# FPGA.net
KiCad netlist of a schematic drawn in Altium Designer
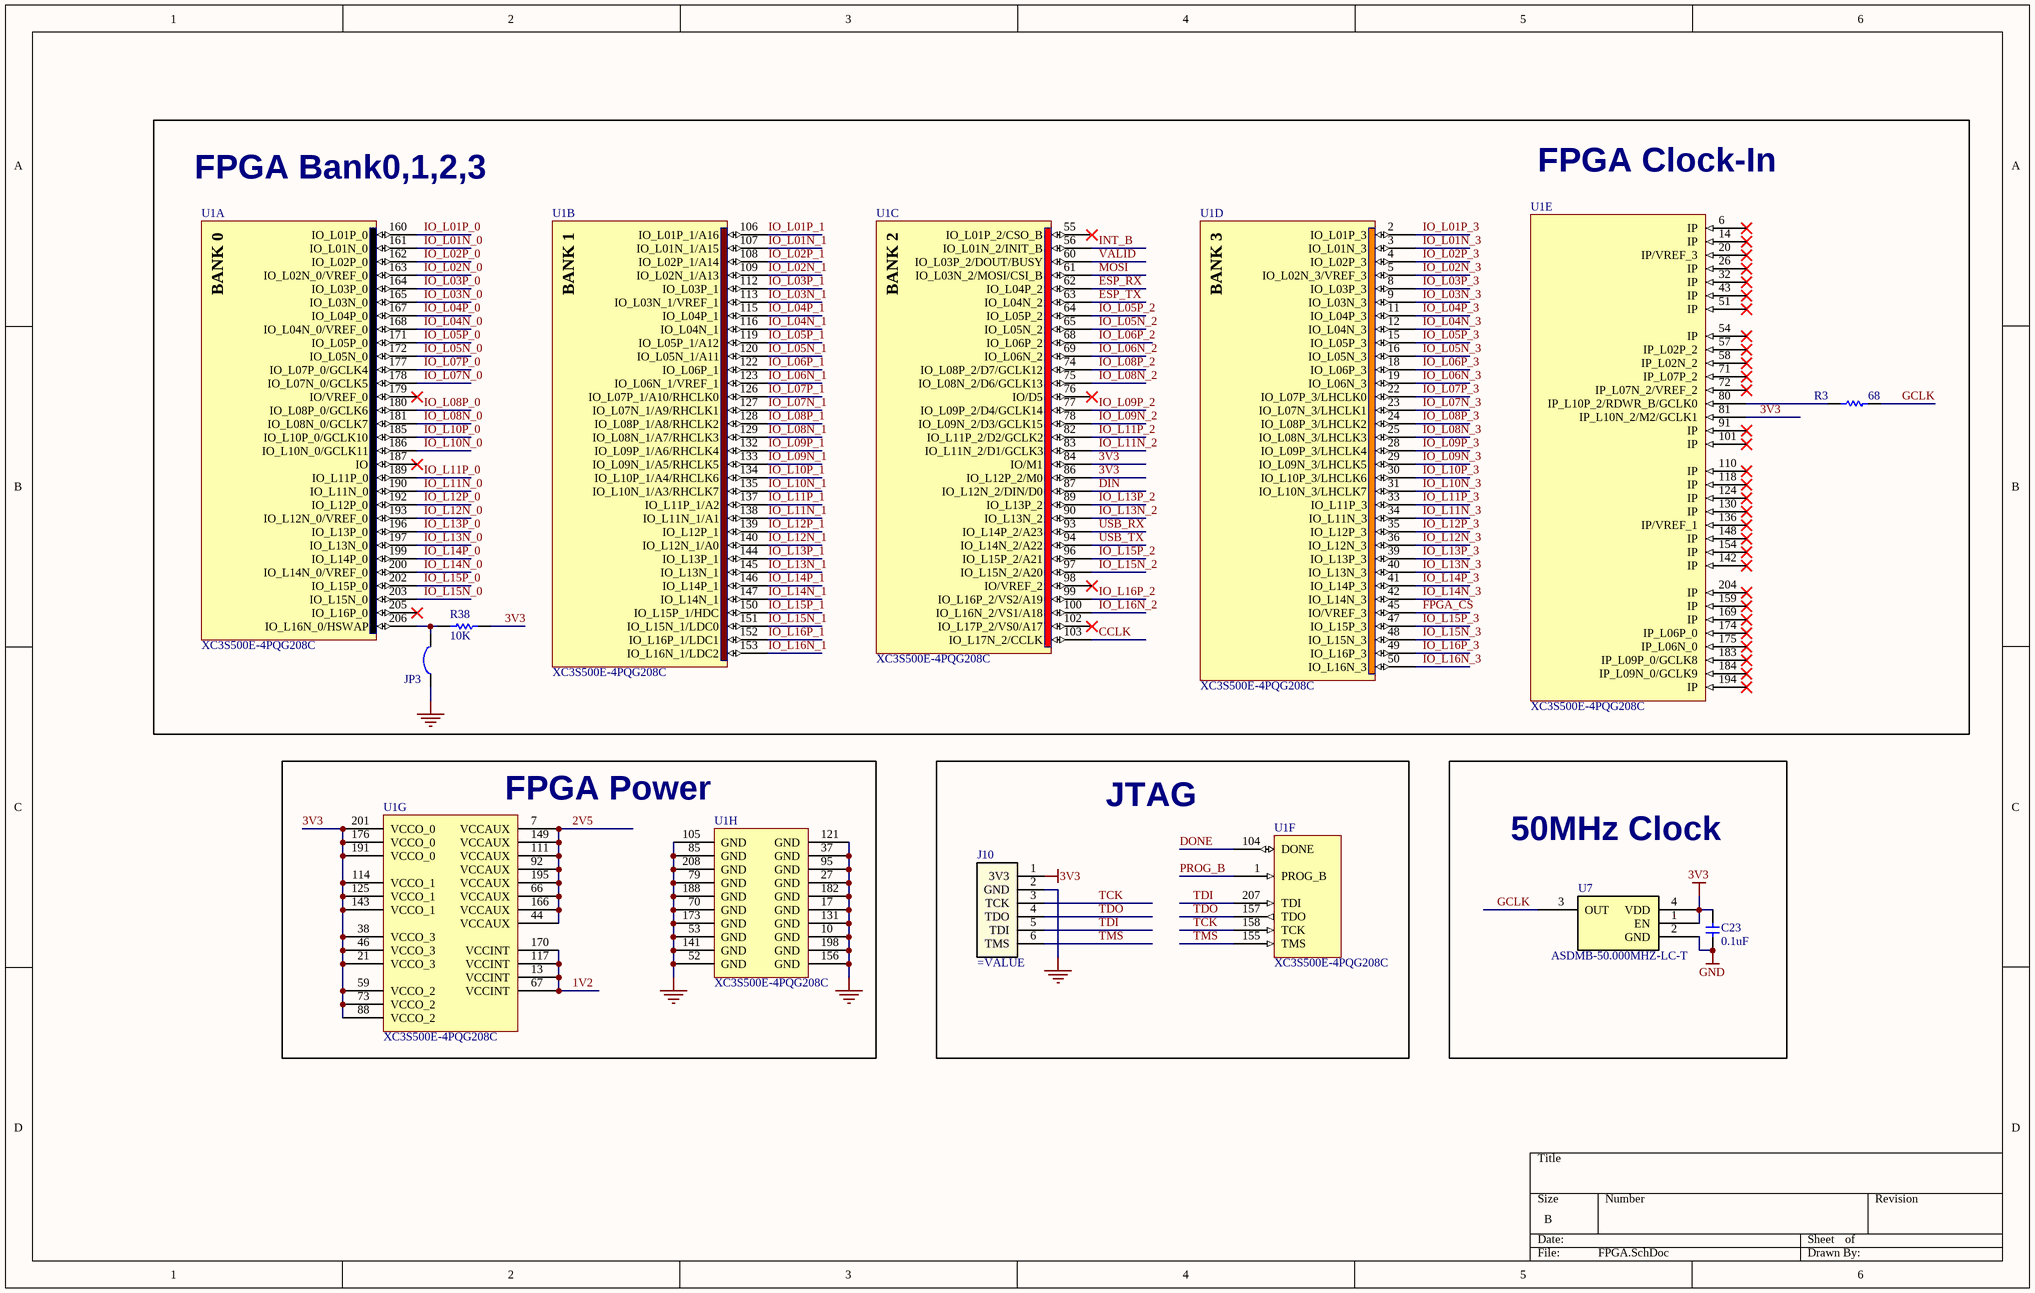
[diagram p0: FPGA.SchDoc]

(export (version "E")
  (design (tool "Eeschema 10.0.6"))
  (components
    (comp (ref "C23")
      (value "0.1uF")
      (footprint "C0603")
      (description "CAP CER .1UF 50V 10% X7R 0603")
      (fields
        (field (name "MANUFACTURER") "Murata Electronics North America")
        (field (name "MANUFACTURER PART NUMBER") "GRM188R71H104KA93D")
      )
      (libsource (lib "eCapacitors") (part "GRM188R71H104KA93D"))
    )
    (comp (ref "J10")
      (value "~")
      (footprint "JTAG - Digilent HS1")
      (description "DIGILENT - 410-205 - PROGRAMMING CABLE, JTAG HS1, USB2")
      (fields
        (field (name "MANUFACTURER") "Samtec")
        (field (name "MANUFACTURER PART NUMBER") "TSW-106-08-G-S-RA")
      )
      (libsource (lib "mConnector") (part "JTAG - Digilent HS1"))
    )
    (comp (ref "JP3")
      (value "Solder Jumper")
      (footprint "SOLDER_JUMPER")
      (description "Solder/Configuration Jumper")
      (fields (field (name "MANUFACTURER") "n/a"))
      (libsource (lib "mConnector") (part "Solder Jumper"))
    )
    (comp (ref "R3")
      (value "68")
      (footprint "R0603")
      (description "Resistor 0603")
      (fields (field (name "MFG") "ROHM"))
      (libsource (lib "Miscellaneous Devices") (part "Res Semi"))
    )
    (comp (ref "R38")
      (value "10K")
      (footprint "R0603")
      (description "Resistor 0603")
      (fields (field (name "MFG") "ROHM"))
      (libsource (lib "Miscellaneous Devices") (part "Res Semi"))
    )
    (comp (ref "U1")
      (value "XC3S500E-4PQG208C")
      (footprint "PQG208_N")
      (description "Spartan-3E 1.2V FPGA, 158 User I/Os, 208-Pin PQFP, Standard Performance, Commercial Grade, Pb-Free")
      (fields (field (name "PUBLISHER") "Altium Limited"))
      (libsource (lib "Xilinx Spartan-3E") (part "XC3S500E-4PQG208C"))
    )
    (comp (ref "U7")
      (value "ASDMB-50.000MHZ-LC-T")
      (footprint "ASDMB - osc")
      (description "OSC MEMS 50.000 MHZ SMD")
      (fields (field (name "MANUFACTURER") "Abracon Corporation"))
      (libsource (lib "eIC") (part "ASDMB-50.000MHZ-LC-T"))
    )
  )
  (nets
    (net (code "1") (name "/1V2") (class "Default")
      (node (ref "U1") (pin "117") (pinfunction "VCCINT_117") (pintype "power_in"))
      (node (ref "U1") (pin "13") (pinfunction "VCCINT_13") (pintype "power_in"))
      (node (ref "U1") (pin "170") (pinfunction "VCCINT_170") (pintype "power_in"))
      (node (ref "U1") (pin "67") (pinfunction "VCCINT_67") (pintype "power_in"))
    )
    (net (code "2") (name "/2V5") (class "Default")
      (node (ref "U1") (pin "111") (pinfunction "VCCAUX_111") (pintype "power_in"))
      (node (ref "U1") (pin "149") (pinfunction "VCCAUX_149") (pintype "power_in"))
      (node (ref "U1") (pin "166") (pinfunction "VCCAUX_166") (pintype "power_in"))
      (node (ref "U1") (pin "195") (pinfunction "VCCAUX_195") (pintype "power_in"))
      (node (ref "U1") (pin "44") (pinfunction "VCCAUX_44") (pintype "power_in"))
      (node (ref "U1") (pin "66") (pinfunction "VCCAUX_66") (pintype "power_in"))
      (node (ref "U1") (pin "7") (pinfunction "VCCAUX_7") (pintype "power_in"))
      (node (ref "U1") (pin "92") (pinfunction "VCCAUX_92") (pintype "power_in"))
    )
    (net (code "3") (name "/CCLK") (class "Default")
      (node (ref "U1") (pin "103") (pinfunction "IO_L17N_2/CCLK_103") (pintype "bidirectional"))
    )
    (net (code "4") (name "/DIN") (class "Default")
      (node (ref "U1") (pin "87") (pinfunction "IO_L12N_2/DIN/D0_87") (pintype "bidirectional"))
    )
    (net (code "5") (name "/DONE") (class "Default")
      (node (ref "U1") (pin "104") (pinfunction "DONE_104") (pintype "bidirectional"))
    )
    (net (code "6") (name "/ESP_RX") (class "Default")
      (node (ref "U1") (pin "62") (pinfunction "IO_L04P_2_62") (pintype "bidirectional"))
    )
    (net (code "7") (name "/ESP_TX") (class "Default")
      (node (ref "U1") (pin "63") (pinfunction "IO_L04N_2_63") (pintype "bidirectional"))
    )
    (net (code "8") (name "/FPGA_CS") (class "Default")
      (node (ref "U1") (pin "45") (pinfunction "IO/VREF_3_45") (pintype "bidirectional"))
    )
    (net (code "9") (name "/GCLK") (class "Default")
      (node (ref "R3") (pin "1") (pinfunction "1_1") (pintype "passive"))
      (node (ref "U7") (pin "3") (pinfunction "OUT_3") (pintype "passive"))
    )
    (net (code "10") (name "/INT_B") (class "Default")
      (node (ref "U1") (pin "56") (pinfunction "IO_L01N_2/INIT_B_56") (pintype "bidirectional"))
    )
    (net (code "11") (name "/IO_L01N_0") (class "Default")
      (node (ref "U1") (pin "161") (pinfunction "IO_L01N_0_161") (pintype "bidirectional"))
    )
    (net (code "12") (name "/IO_L01N_1") (class "Default")
      (node (ref "U1") (pin "107") (pinfunction "IO_L01N_1/A15_107") (pintype "bidirectional"))
    )
    (net (code "13") (name "/IO_L01N_3") (class "Default")
      (node (ref "U1") (pin "3") (pinfunction "IO_L01N_3_3") (pintype "bidirectional"))
    )
    (net (code "14") (name "/IO_L01P_0") (class "Default")
      (node (ref "U1") (pin "160") (pinfunction "IO_L01P_0_160") (pintype "bidirectional"))
    )
    (net (code "15") (name "/IO_L01P_1") (class "Default")
      (node (ref "U1") (pin "106") (pinfunction "IO_L01P_1/A16_106") (pintype "bidirectional"))
    )
    (net (code "16") (name "/IO_L01P_3") (class "Default")
      (node (ref "U1") (pin "2") (pinfunction "IO_L01P_3_2") (pintype "bidirectional"))
    )
    (net (code "17") (name "/IO_L02N_0") (class "Default")
      (node (ref "U1") (pin "163") (pinfunction "IO_L02N_0/VREF_0_163") (pintype "bidirectional"))
    )
    (net (code "18") (name "/IO_L02N_1") (class "Default")
      (node (ref "U1") (pin "109") (pinfunction "IO_L02N_1/A13_109") (pintype "bidirectional"))
    )
    (net (code "19") (name "/IO_L02N_3") (class "Default")
      (node (ref "U1") (pin "5") (pinfunction "IO_L02N_3/VREF_3_5") (pintype "bidirectional"))
    )
    (net (code "20") (name "/IO_L02P_0") (class "Default")
      (node (ref "U1") (pin "162") (pinfunction "IO_L02P_0_162") (pintype "bidirectional"))
    )
    (net (code "21") (name "/IO_L02P_1") (class "Default")
      (node (ref "U1") (pin "108") (pinfunction "IO_L02P_1/A14_108") (pintype "bidirectional"))
    )
    (net (code "22") (name "/IO_L02P_3") (class "Default")
      (node (ref "U1") (pin "4") (pinfunction "IO_L02P_3_4") (pintype "bidirectional"))
    )
    (net (code "23") (name "/IO_L03N_0") (class "Default")
      (node (ref "U1") (pin "165") (pinfunction "IO_L03N_0_165") (pintype "bidirectional"))
    )
    (net (code "24") (name "/IO_L03N_1") (class "Default")
      (node (ref "U1") (pin "113") (pinfunction "IO_L03N_1/VREF_1_113") (pintype "bidirectional"))
    )
    (net (code "25") (name "/IO_L03N_3") (class "Default")
      (node (ref "U1") (pin "9") (pinfunction "IO_L03N_3_9") (pintype "bidirectional"))
    )
    (net (code "26") (name "/IO_L03P_0") (class "Default")
      (node (ref "U1") (pin "164") (pinfunction "IO_L03P_0_164") (pintype "bidirectional"))
    )
    (net (code "27") (name "/IO_L03P_1") (class "Default")
      (node (ref "U1") (pin "112") (pinfunction "IO_L03P_1_112") (pintype "bidirectional"))
    )
    (net (code "28") (name "/IO_L03P_3") (class "Default")
      (node (ref "U1") (pin "8") (pinfunction "IO_L03P_3_8") (pintype "bidirectional"))
    )
    (net (code "29") (name "/IO_L04N_0") (class "Default")
      (node (ref "U1") (pin "168") (pinfunction "IO_L04N_0/VREF_0_168") (pintype "bidirectional"))
    )
    (net (code "30") (name "/IO_L04N_1") (class "Default")
      (node (ref "U1") (pin "116") (pinfunction "IO_L04N_1_116") (pintype "bidirectional"))
    )
    (net (code "31") (name "/IO_L04N_3") (class "Default")
      (node (ref "U1") (pin "12") (pinfunction "IO_L04N_3_12") (pintype "bidirectional"))
    )
    (net (code "32") (name "/IO_L04P_0") (class "Default")
      (node (ref "U1") (pin "167") (pinfunction "IO_L04P_0_167") (pintype "bidirectional"))
    )
    (net (code "33") (name "/IO_L04P_1") (class "Default")
      (node (ref "U1") (pin "115") (pinfunction "IO_L04P_1_115") (pintype "bidirectional"))
    )
    (net (code "34") (name "/IO_L04P_3") (class "Default")
      (node (ref "U1") (pin "11") (pinfunction "IO_L04P_3_11") (pintype "bidirectional"))
    )
    (net (code "35") (name "/IO_L05N_0") (class "Default")
      (node (ref "U1") (pin "172") (pinfunction "IO_L05N_0_172") (pintype "bidirectional"))
    )
    (net (code "36") (name "/IO_L05N_1") (class "Default")
      (node (ref "U1") (pin "120") (pinfunction "IO_L05N_1/A11_120") (pintype "bidirectional"))
    )
    (net (code "37") (name "/IO_L05N_2") (class "Default")
      (node (ref "U1") (pin "65") (pinfunction "IO_L05N_2_65") (pintype "bidirectional"))
    )
    (net (code "38") (name "/IO_L05N_3") (class "Default")
      (node (ref "U1") (pin "16") (pinfunction "IO_L05N_3_16") (pintype "bidirectional"))
    )
    (net (code "39") (name "/IO_L05P_0") (class "Default")
      (node (ref "U1") (pin "171") (pinfunction "IO_L05P_0_171") (pintype "bidirectional"))
    )
    (net (code "40") (name "/IO_L05P_1") (class "Default")
      (node (ref "U1") (pin "119") (pinfunction "IO_L05P_1/A12_119") (pintype "bidirectional"))
    )
    (net (code "41") (name "/IO_L05P_2") (class "Default")
      (node (ref "U1") (pin "64") (pinfunction "IO_L05P_2_64") (pintype "bidirectional"))
    )
    (net (code "42") (name "/IO_L05P_3") (class "Default")
      (node (ref "U1") (pin "15") (pinfunction "IO_L05P_3_15") (pintype "bidirectional"))
    )
    (net (code "43") (name "/IO_L06N_1") (class "Default")
      (node (ref "U1") (pin "123") (pinfunction "IO_L06N_1/VREF_1_123") (pintype "bidirectional"))
    )
    (net (code "44") (name "/IO_L06N_2") (class "Default")
      (node (ref "U1") (pin "69") (pinfunction "IO_L06N_2_69") (pintype "bidirectional"))
    )
    (net (code "45") (name "/IO_L06N_3") (class "Default")
      (node (ref "U1") (pin "19") (pinfunction "IO_L06N_3_19") (pintype "bidirectional"))
    )
    (net (code "46") (name "/IO_L06P_1") (class "Default")
      (node (ref "U1") (pin "122") (pinfunction "IO_L06P_1_122") (pintype "bidirectional"))
    )
    (net (code "47") (name "/IO_L06P_2") (class "Default")
      (node (ref "U1") (pin "68") (pinfunction "IO_L06P_2_68") (pintype "bidirectional"))
    )
    (net (code "48") (name "/IO_L06P_3") (class "Default")
      (node (ref "U1") (pin "18") (pinfunction "IO_L06P_3_18") (pintype "bidirectional"))
    )
    (net (code "49") (name "/IO_L07N_0") (class "Default")
      (node (ref "U1") (pin "178") (pinfunction "IO_L07N_0/GCLK5_178") (pintype "bidirectional"))
    )
    (net (code "50") (name "/IO_L07N_1") (class "Default")
      (node (ref "U1") (pin "127") (pinfunction "IO_L07N_1/A9/RHCLK1_127") (pintype "bidirectional"))
    )
    (net (code "51") (name "/IO_L07N_3") (class "Default")
      (node (ref "U1") (pin "23") (pinfunction "IO_L07N_3/LHCLK1_23") (pintype "bidirectional"))
    )
    (net (code "52") (name "/IO_L07P_0") (class "Default")
      (node (ref "U1") (pin "177") (pinfunction "IO_L07P_0/GCLK4_177") (pintype "bidirectional"))
    )
    (net (code "53") (name "/IO_L07P_1") (class "Default")
      (node (ref "U1") (pin "126") (pinfunction "IO_L07P_1/A10/RHCLK0_126") (pintype "bidirectional"))
    )
    (net (code "54") (name "/IO_L07P_3") (class "Default")
      (node (ref "U1") (pin "22") (pinfunction "IO_L07P_3/LHCLK0_22") (pintype "bidirectional"))
    )
    (net (code "55") (name "/IO_L08N_0") (class "Default")
      (node (ref "U1") (pin "181") (pinfunction "IO_L08N_0/GCLK7_181") (pintype "bidirectional"))
    )
    (net (code "56") (name "/IO_L08N_1") (class "Default")
      (node (ref "U1") (pin "129") (pinfunction "IO_L08N_1/A7/RHCLK3_129") (pintype "bidirectional"))
    )
    (net (code "57") (name "/IO_L08N_2") (class "Default")
      (node (ref "U1") (pin "75") (pinfunction "IO_L08N_2/D6/GCLK13_75") (pintype "bidirectional"))
    )
    (net (code "58") (name "/IO_L08N_3") (class "Default")
      (node (ref "U1") (pin "25") (pinfunction "IO_L08N_3/LHCLK3_25") (pintype "bidirectional"))
    )
    (net (code "59") (name "/IO_L08P_0") (class "Default")
      (node (ref "U1") (pin "180") (pinfunction "IO_L08P_0/GCLK6_180") (pintype "bidirectional"))
    )
    (net (code "60") (name "/IO_L08P_1") (class "Default")
      (node (ref "U1") (pin "128") (pinfunction "IO_L08P_1/A8/RHCLK2_128") (pintype "bidirectional"))
    )
    (net (code "61") (name "/IO_L08P_2") (class "Default")
      (node (ref "U1") (pin "74") (pinfunction "IO_L08P_2/D7/GCLK12_74") (pintype "bidirectional"))
    )
    (net (code "62") (name "/IO_L08P_3") (class "Default")
      (node (ref "U1") (pin "24") (pinfunction "IO_L08P_3/LHCLK2_24") (pintype "bidirectional"))
    )
    (net (code "63") (name "/IO_L09N_1") (class "Default")
      (node (ref "U1") (pin "133") (pinfunction "IO_L09N_1/A5/RHCLK5_133") (pintype "bidirectional"))
    )
    (net (code "64") (name "/IO_L09N_2") (class "Default")
      (node (ref "U1") (pin "78") (pinfunction "IO_L09N_2/D3/GCLK15_78") (pintype "bidirectional"))
    )
    (net (code "65") (name "/IO_L09N_3") (class "Default")
      (node (ref "U1") (pin "29") (pinfunction "IO_L09N_3/LHCLK5_29") (pintype "bidirectional"))
    )
    (net (code "66") (name "/IO_L09P_1") (class "Default")
      (node (ref "U1") (pin "132") (pinfunction "IO_L09P_1/A6/RHCLK4_132") (pintype "bidirectional"))
    )
    (net (code "67") (name "/IO_L09P_2") (class "Default")
      (node (ref "U1") (pin "77") (pinfunction "IO_L09P_2/D4/GCLK14_77") (pintype "bidirectional"))
    )
    (net (code "68") (name "/IO_L09P_3") (class "Default")
      (node (ref "U1") (pin "28") (pinfunction "IO_L09P_3/LHCLK4_28") (pintype "bidirectional"))
    )
    (net (code "69") (name "/IO_L10N_0") (class "Default")
      (node (ref "U1") (pin "186") (pinfunction "IO_L10N_0/GCLK11_186") (pintype "bidirectional"))
    )
    (net (code "70") (name "/IO_L10N_1") (class "Default")
      (node (ref "U1") (pin "135") (pinfunction "IO_L10N_1/A3/RHCLK7_135") (pintype "bidirectional"))
    )
    (net (code "71") (name "/IO_L10N_3") (class "Default")
      (node (ref "U1") (pin "31") (pinfunction "IO_L10N_3/LHCLK7_31") (pintype "bidirectional"))
    )
    (net (code "72") (name "/IO_L10P_0") (class "Default")
      (node (ref "U1") (pin "185") (pinfunction "IO_L10P_0/GCLK10_185") (pintype "bidirectional"))
    )
    (net (code "73") (name "/IO_L10P_1") (class "Default")
      (node (ref "U1") (pin "134") (pinfunction "IO_L10P_1/A4/RHCLK6_134") (pintype "bidirectional"))
    )
    (net (code "74") (name "/IO_L10P_3") (class "Default")
      (node (ref "U1") (pin "30") (pinfunction "IO_L10P_3/LHCLK6_30") (pintype "bidirectional"))
    )
    (net (code "75") (name "/IO_L11N_0") (class "Default")
      (node (ref "U1") (pin "190") (pinfunction "IO_L11N_0_190") (pintype "bidirectional"))
    )
    (net (code "76") (name "/IO_L11N_1") (class "Default")
      (node (ref "U1") (pin "138") (pinfunction "IO_L11N_1/A1_138") (pintype "bidirectional"))
    )
    (net (code "77") (name "/IO_L11N_2") (class "Default")
      (node (ref "U1") (pin "83") (pinfunction "IO_L11N_2/D1/GCLK3_83") (pintype "bidirectional"))
    )
    (net (code "78") (name "/IO_L11N_3") (class "Default")
      (node (ref "U1") (pin "34") (pinfunction "IO_L11N_3_34") (pintype "bidirectional"))
    )
    (net (code "79") (name "/IO_L11P_0") (class "Default")
      (node (ref "U1") (pin "189") (pinfunction "IO_L11P_0_189") (pintype "bidirectional"))
    )
    (net (code "80") (name "/IO_L11P_1") (class "Default")
      (node (ref "U1") (pin "137") (pinfunction "IO_L11P_1/A2_137") (pintype "bidirectional"))
    )
    (net (code "81") (name "/IO_L11P_2") (class "Default")
      (node (ref "U1") (pin "82") (pinfunction "IO_L11P_2/D2/GCLK2_82") (pintype "bidirectional"))
    )
    (net (code "82") (name "/IO_L11P_3") (class "Default")
      (node (ref "U1") (pin "33") (pinfunction "IO_L11P_3_33") (pintype "bidirectional"))
    )
    (net (code "83") (name "/IO_L12N_0") (class "Default")
      (node (ref "U1") (pin "193") (pinfunction "IO_L12N_0/VREF_0_193") (pintype "bidirectional"))
    )
    (net (code "84") (name "/IO_L12N_1") (class "Default")
      (node (ref "U1") (pin "140") (pinfunction "IO_L12N_1/A0_140") (pintype "bidirectional"))
    )
    (net (code "85") (name "/IO_L12N_3") (class "Default")
      (node (ref "U1") (pin "36") (pinfunction "IO_L12N_3_36") (pintype "bidirectional"))
    )
    (net (code "86") (name "/IO_L12P_0") (class "Default")
      (node (ref "U1") (pin "192") (pinfunction "IO_L12P_0_192") (pintype "bidirectional"))
    )
    (net (code "87") (name "/IO_L12P_1") (class "Default")
      (node (ref "U1") (pin "139") (pinfunction "IO_L12P_1_139") (pintype "bidirectional"))
    )
    (net (code "88") (name "/IO_L12P_3") (class "Default")
      (node (ref "U1") (pin "35") (pinfunction "IO_L12P_3_35") (pintype "bidirectional"))
    )
    (net (code "89") (name "/IO_L13N_0") (class "Default")
      (node (ref "U1") (pin "197") (pinfunction "IO_L13N_0_197") (pintype "bidirectional"))
    )
    (net (code "90") (name "/IO_L13N_1") (class "Default")
      (node (ref "U1") (pin "145") (pinfunction "IO_L13N_1_145") (pintype "bidirectional"))
    )
    (net (code "91") (name "/IO_L13N_2") (class "Default")
      (node (ref "U1") (pin "90") (pinfunction "IO_L13N_2_90") (pintype "bidirectional"))
    )
    (net (code "92") (name "/IO_L13N_3") (class "Default")
      (node (ref "U1") (pin "40") (pinfunction "IO_L13N_3_40") (pintype "bidirectional"))
    )
    (net (code "93") (name "/IO_L13P_0") (class "Default")
      (node (ref "U1") (pin "196") (pinfunction "IO_L13P_0_196") (pintype "bidirectional"))
    )
    (net (code "94") (name "/IO_L13P_1") (class "Default")
      (node (ref "U1") (pin "144") (pinfunction "IO_L13P_1_144") (pintype "bidirectional"))
    )
    (net (code "95") (name "/IO_L13P_2") (class "Default")
      (node (ref "U1") (pin "89") (pinfunction "IO_L13P_2_89") (pintype "bidirectional"))
    )
    (net (code "96") (name "/IO_L13P_3") (class "Default")
      (node (ref "U1") (pin "39") (pinfunction "IO_L13P_3_39") (pintype "bidirectional"))
    )
    (net (code "97") (name "/IO_L14N_0") (class "Default")
      (node (ref "U1") (pin "200") (pinfunction "IO_L14N_0/VREF_0_200") (pintype "bidirectional"))
    )
    (net (code "98") (name "/IO_L14N_1") (class "Default")
      (node (ref "U1") (pin "147") (pinfunction "IO_L14N_1_147") (pintype "bidirectional"))
    )
    (net (code "99") (name "/IO_L14N_3") (class "Default")
      (node (ref "U1") (pin "42") (pinfunction "IO_L14N_3_42") (pintype "bidirectional"))
    )
    (net (code "100") (name "/IO_L14P_0") (class "Default")
      (node (ref "U1") (pin "199") (pinfunction "IO_L14P_0_199") (pintype "bidirectional"))
    )
    (net (code "101") (name "/IO_L14P_1") (class "Default")
      (node (ref "U1") (pin "146") (pinfunction "IO_L14P_1_146") (pintype "bidirectional"))
    )
    (net (code "102") (name "/IO_L14P_3") (class "Default")
      (node (ref "U1") (pin "41") (pinfunction "IO_L14P_3_41") (pintype "bidirectional"))
    )
    (net (code "103") (name "/IO_L15N_0") (class "Default")
      (node (ref "U1") (pin "203") (pinfunction "IO_L15N_0_203") (pintype "bidirectional"))
    )
    (net (code "104") (name "/IO_L15N_1") (class "Default")
      (node (ref "U1") (pin "151") (pinfunction "IO_L15N_1/LDC0_151") (pintype "bidirectional"))
    )
    (net (code "105") (name "/IO_L15N_2") (class "Default")
      (node (ref "U1") (pin "97") (pinfunction "IO_L15N_2/A20_97") (pintype "bidirectional"))
    )
    (net (code "106") (name "/IO_L15N_3") (class "Default")
      (node (ref "U1") (pin "48") (pinfunction "IO_L15N_3_48") (pintype "bidirectional"))
    )
    (net (code "107") (name "/IO_L15P_0") (class "Default")
      (node (ref "U1") (pin "202") (pinfunction "IO_L15P_0_202") (pintype "bidirectional"))
    )
    (net (code "108") (name "/IO_L15P_1") (class "Default")
      (node (ref "U1") (pin "150") (pinfunction "IO_L15P_1/HDC_150") (pintype "bidirectional"))
    )
    (net (code "109") (name "/IO_L15P_2") (class "Default")
      (node (ref "U1") (pin "96") (pinfunction "IO_L15P_2/A21_96") (pintype "bidirectional"))
    )
    (net (code "110") (name "/IO_L15P_3") (class "Default")
      (node (ref "U1") (pin "47") (pinfunction "IO_L15P_3_47") (pintype "bidirectional"))
    )
    (net (code "111") (name "/IO_L16N_1") (class "Default")
      (node (ref "U1") (pin "153") (pinfunction "IO_L16N_1/LDC2_153") (pintype "bidirectional"))
    )
    (net (code "112") (name "/IO_L16N_2") (class "Default")
      (node (ref "U1") (pin "100") (pinfunction "IO_L16N_2/VS1/A18_100") (pintype "bidirectional"))
    )
    (net (code "113") (name "/IO_L16N_3") (class "Default")
      (node (ref "U1") (pin "50") (pinfunction "IO_L16N_3_50") (pintype "bidirectional"))
    )
    (net (code "114") (name "/IO_L16P_1") (class "Default")
      (node (ref "U1") (pin "152") (pinfunction "IO_L16P_1/LDC1_152") (pintype "bidirectional"))
    )
    (net (code "115") (name "/IO_L16P_2") (class "Default")
      (node (ref "U1") (pin "99") (pinfunction "IO_L16P_2/VS2/A19_99") (pintype "bidirectional"))
    )
    (net (code "116") (name "/IO_L16P_3") (class "Default")
      (node (ref "U1") (pin "49") (pinfunction "IO_L16P_3_49") (pintype "bidirectional"))
    )
    (net (code "117") (name "/MOSI") (class "Default")
      (node (ref "U1") (pin "61") (pinfunction "IO_L03N_2/MOSI/CSI_B_61") (pintype "bidirectional"))
    )
    (net (code "118") (name "/PROG_B") (class "Default")
      (node (ref "U1") (pin "1") (pinfunction "PROG_B_1") (pintype "input"))
    )
    (net (code "119") (name "/TCK") (class "Default")
      (node (ref "J10") (pin "3") (pinfunction "TCK_3") (pintype "passive"))
      (node (ref "U1") (pin "158") (pinfunction "TCK_158") (pintype "input"))
    )
    (net (code "120") (name "/TDI") (class "Default")
      (node (ref "J10") (pin "5") (pinfunction "TDI_5") (pintype "passive"))
      (node (ref "U1") (pin "207") (pinfunction "TDI_207") (pintype "input"))
    )
    (net (code "121") (name "/TDO") (class "Default")
      (node (ref "J10") (pin "4") (pinfunction "TDO_4") (pintype "passive"))
      (node (ref "U1") (pin "157") (pinfunction "TDO_157") (pintype "output"))
    )
    (net (code "122") (name "/TMS") (class "Default")
      (node (ref "J10") (pin "6") (pinfunction "TMS_6") (pintype "passive"))
      (node (ref "U1") (pin "155") (pinfunction "TMS_155") (pintype "input"))
    )
    (net (code "123") (name "/USB_RX") (class "Default")
      (node (ref "U1") (pin "93") (pinfunction "IO_L14P_2/A23_93") (pintype "bidirectional"))
    )
    (net (code "124") (name "/USB_TX") (class "Default")
      (node (ref "U1") (pin "94") (pinfunction "IO_L14N_2/A22_94") (pintype "bidirectional"))
    )
    (net (code "125") (name "/VALID") (class "Default")
      (node (ref "U1") (pin "60") (pinfunction "IO_L03P_2/DOUT/BUSY_60") (pintype "bidirectional"))
    )
    (net (code "126") (name "3V3") (class "Default")
      (node (ref "C23") (pin "2") (pinfunction "2_2") (pintype "passive"))
      (node (ref "J10") (pin "1") (pinfunction "3V3_1") (pintype "passive"))
      (node (ref "R38") (pin "2") (pinfunction "2_2") (pintype "passive"))
      (node (ref "U1") (pin "114") (pinfunction "VCCO_1_114") (pintype "power_in"))
      (node (ref "U1") (pin "125") (pinfunction "VCCO_1_125") (pintype "power_in"))
      (node (ref "U1") (pin "143") (pinfunction "VCCO_1_143") (pintype "power_in"))
      (node (ref "U1") (pin "176") (pinfunction "VCCO_0_176") (pintype "power_in"))
      (node (ref "U1") (pin "191") (pinfunction "VCCO_0_191") (pintype "power_in"))
      (node (ref "U1") (pin "201") (pinfunction "VCCO_0_201") (pintype "power_in"))
      (node (ref "U1") (pin "21") (pinfunction "VCCO_3_21") (pintype "power_in"))
      (node (ref "U1") (pin "38") (pinfunction "VCCO_3_38") (pintype "power_in"))
      (node (ref "U1") (pin "46") (pinfunction "VCCO_3_46") (pintype "power_in"))
      (node (ref "U1") (pin "59") (pinfunction "VCCO_2_59") (pintype "power_in"))
      (node (ref "U1") (pin "73") (pinfunction "VCCO_2_73") (pintype "power_in"))
      (node (ref "U1") (pin "81") (pinfunction "IP_L10N_2/M2/GCLK1_81") (pintype "input"))
      (node (ref "U1") (pin "84") (pinfunction "IO/M1_84") (pintype "bidirectional"))
      (node (ref "U1") (pin "86") (pinfunction "IO_L12P_2/M0_86") (pintype "bidirectional"))
      (node (ref "U1") (pin "88") (pinfunction "VCCO_2_88") (pintype "power_in"))
      (node (ref "U7") (pin "1") (pinfunction "EN_1") (pintype "passive"))
      (node (ref "U7") (pin "4") (pinfunction "VDD_4") (pintype "passive"))
    )
    (net (code "127") (name "GND") (class "Default")
      (node (ref "C23") (pin "1") (pinfunction "1_1") (pintype "passive"))
      (node (ref "J10") (pin "2") (pinfunction "GND_2") (pintype "passive"))
      (node (ref "JP3") (pin "2") (pinfunction "2_2") (pintype "passive"))
      (node (ref "U1") (pin "10") (pinfunction "GND_10") (pintype "power_in"))
      (node (ref "U1") (pin "105") (pinfunction "GND_105") (pintype "power_in"))
      (node (ref "U1") (pin "121") (pinfunction "GND_121") (pintype "power_in"))
      (node (ref "U1") (pin "131") (pinfunction "GND_131") (pintype "power_in"))
      (node (ref "U1") (pin "141") (pinfunction "GND_141") (pintype "power_in"))
      (node (ref "U1") (pin "156") (pinfunction "GND_156") (pintype "power_in"))
      (node (ref "U1") (pin "17") (pinfunction "GND_17") (pintype "power_in"))
      (node (ref "U1") (pin "173") (pinfunction "GND_173") (pintype "power_in"))
      (node (ref "U1") (pin "182") (pinfunction "GND_182") (pintype "power_in"))
      (node (ref "U1") (pin "188") (pinfunction "GND_188") (pintype "power_in"))
      (node (ref "U1") (pin "198") (pinfunction "GND_198") (pintype "power_in"))
      (node (ref "U1") (pin "208") (pinfunction "GND_208") (pintype "power_in"))
      (node (ref "U1") (pin "27") (pinfunction "GND_27") (pintype "power_in"))
      (node (ref "U1") (pin "37") (pinfunction "GND_37") (pintype "power_in"))
      (node (ref "U1") (pin "52") (pinfunction "GND_52") (pintype "power_in"))
      (node (ref "U1") (pin "53") (pinfunction "GND_53") (pintype "power_in"))
      (node (ref "U1") (pin "70") (pinfunction "GND_70") (pintype "power_in"))
      (node (ref "U1") (pin "79") (pinfunction "GND_79") (pintype "power_in"))
      (node (ref "U1") (pin "85") (pinfunction "GND_85") (pintype "power_in"))
      (node (ref "U1") (pin "95") (pinfunction "GND_95") (pintype "power_in"))
      (node (ref "U7") (pin "2") (pinfunction "GND_2") (pintype "passive"))
    )
    (net (code "128") (name "Net-(U1A-IO_L16N_0{slash}HSWAP)") (class "Default")
      (node (ref "JP3") (pin "1") (pinfunction "1_1") (pintype "passive"))
      (node (ref "R38") (pin "1") (pinfunction "1_1") (pintype "passive"))
      (node (ref "U1") (pin "206") (pinfunction "IO_L16N_0/HSWAP_206") (pintype "bidirectional"))
    )
    (net (code "129") (name "Net-(U1E-IP_L10P_2{slash}RDWR_B{slash}GCLK0)") (class "Default")
      (node (ref "R3") (pin "2") (pinfunction "2_2") (pintype "passive"))
      (node (ref "U1") (pin "80") (pinfunction "IP_L10P_2/RDWR_B/GCLK0_80") (pintype "input"))
    )
    (net (code "130") (name "unconnected-(U1A-IO-Pad187)") (class "Default")
      (node (ref "U1") (pin "187") (pinfunction "IO_187") (pintype "bidirectional+no_connect"))
    )
    (net (code "131") (name "unconnected-(U1A-IO_L16P_0-Pad205)") (class "Default")
      (node (ref "U1") (pin "205") (pinfunction "IO_L16P_0_205") (pintype "bidirectional+no_connect"))
    )
    (net (code "132") (name "unconnected-(U1A-IO{slash}VREF_0-Pad179)") (class "Default")
      (node (ref "U1") (pin "179") (pinfunction "IO/VREF_0_179") (pintype "bidirectional+no_connect"))
    )
    (net (code "133") (name "unconnected-(U1C-IO_L01P_2{slash}CSO_B-Pad55)") (class "Default")
      (node (ref "U1") (pin "55") (pinfunction "IO_L01P_2/CSO_B_55") (pintype "bidirectional+no_connect"))
    )
    (net (code "134") (name "unconnected-(U1C-IO_L17P_2{slash}VS0{slash}A17-Pad102)") (class "Default")
      (node (ref "U1") (pin "102") (pinfunction "IO_L17P_2/VS0/A17_102") (pintype "bidirectional+no_connect"))
    )
    (net (code "135") (name "unconnected-(U1C-IO{slash}D5-Pad76)") (class "Default")
      (node (ref "U1") (pin "76") (pinfunction "IO/D5_76") (pintype "bidirectional+no_connect"))
    )
    (net (code "136") (name "unconnected-(U1C-IO{slash}VREF_2-Pad98)") (class "Default")
      (node (ref "U1") (pin "98") (pinfunction "IO/VREF_2_98") (pintype "bidirectional+no_connect"))
    )
    (net (code "137") (name "unconnected-(U1E-IP-Pad6)") (class "Default")
      (node (ref "U1") (pin "6") (pinfunction "IP_6") (pintype "input+no_connect"))
    )
    (net (code "138") (name "unconnected-(U1E-IP-Pad14)") (class "Default")
      (node (ref "U1") (pin "14") (pinfunction "IP_14") (pintype "input+no_connect"))
    )
    (net (code "139") (name "unconnected-(U1E-IP-Pad26)") (class "Default")
      (node (ref "U1") (pin "26") (pinfunction "IP_26") (pintype "input+no_connect"))
    )
    (net (code "140") (name "unconnected-(U1E-IP-Pad32)") (class "Default")
      (node (ref "U1") (pin "32") (pinfunction "IP_32") (pintype "input+no_connect"))
    )
    (net (code "141") (name "unconnected-(U1E-IP-Pad43)") (class "Default")
      (node (ref "U1") (pin "43") (pinfunction "IP_43") (pintype "input+no_connect"))
    )
    (net (code "142") (name "unconnected-(U1E-IP-Pad51)") (class "Default")
      (node (ref "U1") (pin "51") (pinfunction "IP_51") (pintype "input+no_connect"))
    )
    (net (code "143") (name "unconnected-(U1E-IP-Pad54)") (class "Default")
      (node (ref "U1") (pin "54") (pinfunction "IP_54") (pintype "input+no_connect"))
    )
    (net (code "144") (name "unconnected-(U1E-IP-Pad91)") (class "Default")
      (node (ref "U1") (pin "91") (pinfunction "IP_91") (pintype "input+no_connect"))
    )
    (net (code "145") (name "unconnected-(U1E-IP-Pad101)") (class "Default")
      (node (ref "U1") (pin "101") (pinfunction "IP_101") (pintype "input+no_connect"))
    )
    (net (code "146") (name "unconnected-(U1E-IP-Pad110)") (class "Default")
      (node (ref "U1") (pin "110") (pinfunction "IP_110") (pintype "input+no_connect"))
    )
    (net (code "147") (name "unconnected-(U1E-IP-Pad118)") (class "Default")
      (node (ref "U1") (pin "118") (pinfunction "IP_118") (pintype "input+no_connect"))
    )
    (net (code "148") (name "unconnected-(U1E-IP-Pad124)") (class "Default")
      (node (ref "U1") (pin "124") (pinfunction "IP_124") (pintype "input+no_connect"))
    )
    (net (code "149") (name "unconnected-(U1E-IP-Pad130)") (class "Default")
      (node (ref "U1") (pin "130") (pinfunction "IP_130") (pintype "input+no_connect"))
    )
    (net (code "150") (name "unconnected-(U1E-IP-Pad142)") (class "Default")
      (node (ref "U1") (pin "142") (pinfunction "IP_142") (pintype "input+no_connect"))
    )
    (net (code "151") (name "unconnected-(U1E-IP-Pad148)") (class "Default")
      (node (ref "U1") (pin "148") (pinfunction "IP_148") (pintype "input+no_connect"))
    )
    (net (code "152") (name "unconnected-(U1E-IP-Pad154)") (class "Default")
      (node (ref "U1") (pin "154") (pinfunction "IP_154") (pintype "input+no_connect"))
    )
    (net (code "153") (name "unconnected-(U1E-IP-Pad159)") (class "Default")
      (node (ref "U1") (pin "159") (pinfunction "IP_159") (pintype "input+no_connect"))
    )
    (net (code "154") (name "unconnected-(U1E-IP-Pad169)") (class "Default")
      (node (ref "U1") (pin "169") (pinfunction "IP_169") (pintype "input+no_connect"))
    )
    (net (code "155") (name "unconnected-(U1E-IP-Pad194)") (class "Default")
      (node (ref "U1") (pin "194") (pinfunction "IP_194") (pintype "input+no_connect"))
    )
    (net (code "156") (name "unconnected-(U1E-IP-Pad204)") (class "Default")
      (node (ref "U1") (pin "204") (pinfunction "IP_204") (pintype "input+no_connect"))
    )
    (net (code "157") (name "unconnected-(U1E-IP_L02N_2-Pad58)") (class "Default")
      (node (ref "U1") (pin "58") (pinfunction "IP_L02N_2_58") (pintype "input+no_connect"))
    )
    (net (code "158") (name "unconnected-(U1E-IP_L02P_2-Pad57)") (class "Default")
      (node (ref "U1") (pin "57") (pinfunction "IP_L02P_2_57") (pintype "input+no_connect"))
    )
    (net (code "159") (name "unconnected-(U1E-IP_L06N_0-Pad175)") (class "Default")
      (node (ref "U1") (pin "175") (pinfunction "IP_L06N_0_175") (pintype "input+no_connect"))
    )
    (net (code "160") (name "unconnected-(U1E-IP_L06P_0-Pad174)") (class "Default")
      (node (ref "U1") (pin "174") (pinfunction "IP_L06P_0_174") (pintype "input+no_connect"))
    )
    (net (code "161") (name "unconnected-(U1E-IP_L07N_2{slash}VREF_2-Pad72)") (class "Default")
      (node (ref "U1") (pin "72") (pinfunction "IP_L07N_2/VREF_2_72") (pintype "input+no_connect"))
    )
    (net (code "162") (name "unconnected-(U1E-IP_L07P_2-Pad71)") (class "Default")
      (node (ref "U1") (pin "71") (pinfunction "IP_L07P_2_71") (pintype "input+no_connect"))
    )
    (net (code "163") (name "unconnected-(U1E-IP_L09N_0{slash}GCLK9-Pad184)") (class "Default")
      (node (ref "U1") (pin "184") (pinfunction "IP_L09N_0/GCLK9_184") (pintype "input+no_connect"))
    )
    (net (code "164") (name "unconnected-(U1E-IP_L09P_0{slash}GCLK8-Pad183)") (class "Default")
      (node (ref "U1") (pin "183") (pinfunction "IP_L09P_0/GCLK8_183") (pintype "input+no_connect"))
    )
    (net (code "165") (name "unconnected-(U1E-IP{slash}VREF_1-Pad136)") (class "Default")
      (node (ref "U1") (pin "136") (pinfunction "IP/VREF_1_136") (pintype "input+no_connect"))
    )
    (net (code "166") (name "unconnected-(U1E-IP{slash}VREF_3-Pad20)") (class "Default")
      (node (ref "U1") (pin "20") (pinfunction "IP/VREF_3_20") (pintype "input+no_connect"))
    )
  )
)
